# wireless_power_meter.net
KiCad netlist of a schematic drawn in EAGLE
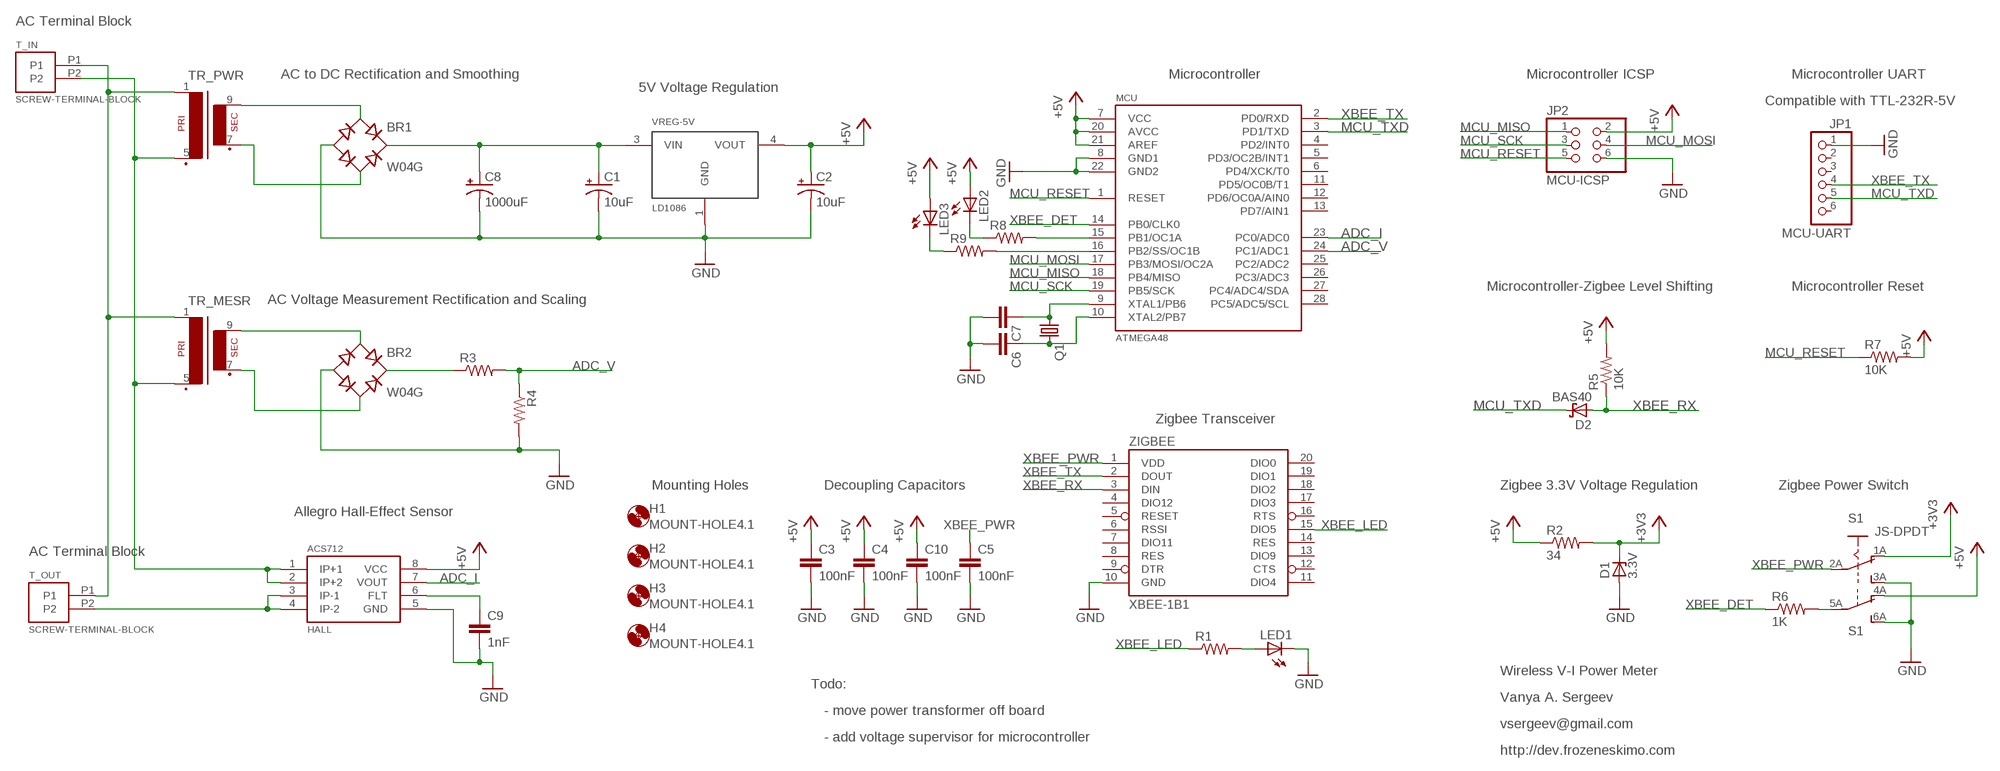
[diagram p0: schematic, sheet 1]

(export (version "E")
  (design (tool "Eeschema 10.0.6"))
  (components
    (comp (ref "BR1")
      (value "W04G")
      (footprint "eagle-import:WOG")
      (libsource (lib "eagle-import") (part "WG04"))
    )
    (comp (ref "BR2")
      (value "W04G")
      (footprint "eagle-import:WOG")
      (libsource (lib "eagle-import") (part "WG04"))
    )
    (comp (ref "C1")
      (value "10uF")
      (footprint "eagle-import:E2,5-5")
      (libsource (lib "eagle-import") (part "CPOL-USE2.5-5"))
    )
    (comp (ref "C2")
      (value "10uF")
      (footprint "eagle-import:E2,5-5")
      (libsource (lib "eagle-import") (part "CPOL-USE2.5-5"))
    )
    (comp (ref "C3")
      (value "100nF")
      (footprint "eagle-import:C0805")
      (libsource (lib "eagle-import") (part "C-EUC0805"))
    )
    (comp (ref "C4")
      (value "100nF")
      (footprint "eagle-import:C0805")
      (libsource (lib "eagle-import") (part "C-EUC0805"))
    )
    (comp (ref "C5")
      (value "100nF")
      (footprint "eagle-import:C0805")
      (libsource (lib "eagle-import") (part "C-EUC0805"))
    )
    (comp (ref "C6")
      (value "C-EUC0805")
      (footprint "eagle-import:C0805")
      (libsource (lib "eagle-import") (part "C-EUC0805"))
    )
    (comp (ref "C7")
      (value "C-EUC0805")
      (footprint "eagle-import:C0805")
      (libsource (lib "eagle-import") (part "C-EUC0805"))
    )
    (comp (ref "C8")
      (value "1000uF")
      (footprint "eagle-import:E5-13")
      (libsource (lib "eagle-import") (part "CPOL-USE5-13"))
    )
    (comp (ref "C9")
      (value "1nF")
      (footprint "eagle-import:C0805")
      (libsource (lib "eagle-import") (part "C-EUC0805"))
    )
    (comp (ref "C10")
      (value "100nF")
      (footprint "eagle-import:C0805")
      (libsource (lib "eagle-import") (part "C-EUC0805"))
    )
    (comp (ref "D1")
      (value "3.3V")
      (footprint "eagle-import:SOT23")
      (libsource (lib "eagle-import") (part "ZENER-DIODESOT23"))
    )
    (comp (ref "D2")
      (value "BAS40")
      (footprint "eagle-import:SOT23")
      (libsource (lib "eagle-import") (part "BAS40"))
    )
    (comp (ref "H1")
      (value "MOUNT-HOLE4.1")
      (footprint "eagle-import:4,1")
      (libsource (lib "eagle-import") (part "MOUNT-HOLE4.1"))
    )
    (comp (ref "H2")
      (value "MOUNT-HOLE4.1")
      (footprint "eagle-import:4,1")
      (libsource (lib "eagle-import") (part "MOUNT-HOLE4.1"))
    )
    (comp (ref "H3")
      (value "MOUNT-HOLE4.1")
      (footprint "eagle-import:4,1")
      (libsource (lib "eagle-import") (part "MOUNT-HOLE4.1"))
    )
    (comp (ref "H4")
      (value "MOUNT-HOLE4.1")
      (footprint "eagle-import:4,1")
      (libsource (lib "eagle-import") (part "MOUNT-HOLE4.1"))
    )
    (comp (ref "HALL")
      (value "ACS712")
      (footprint "eagle-import:SO8")
      (libsource (lib "eagle-import") (part "ACS712"))
    )
    (comp (ref "JP1")
      (value "MCU-UART")
      (footprint "eagle-import:1X06")
      (libsource (lib "eagle-import") (part "PINHD-1X6"))
    )
    (comp (ref "JP2")
      (value "MCU-ICSP")
      (footprint "eagle-import:2X03")
      (libsource (lib "eagle-import") (part "PINHD-2X3"))
    )
    (comp (ref "LED1")
      (value "LEDCHIPLED_0805")
      (footprint "eagle-import:CHIPLED_0805")
      (libsource (lib "eagle-import") (part "LEDCHIPLED_0805"))
    )
    (comp (ref "LED2")
      (value "LEDCHIPLED_0805")
      (footprint "eagle-import:CHIPLED_0805")
      (libsource (lib "eagle-import") (part "LEDCHIPLED_0805"))
    )
    (comp (ref "LED3")
      (value "LEDCHIPLED_0805")
      (footprint "eagle-import:CHIPLED_0805")
      (libsource (lib "eagle-import") (part "LEDCHIPLED_0805"))
    )
    (comp (ref "MCU")
      (value "ATMEGA48")
      (footprint "eagle-import:DIL28-3")
      (libsource (lib "eagle-import") (part "ATMEGA48"))
    )
    (comp (ref "Q1")
      (value "CRYSTALTC26H")
      (footprint "eagle-import:TC26H")
      (libsource (lib "eagle-import") (part "CRYSTALTC26H"))
    )
    (comp (ref "R1")
      (value "R-US_R0805")
      (footprint "eagle-import:R0805")
      (libsource (lib "eagle-import") (part "R-US_R0805"))
    )
    (comp (ref "R2")
      (value "34")
      (footprint "eagle-import:R0805")
      (libsource (lib "eagle-import") (part "R-US_R0805"))
    )
    (comp (ref "R3")
      (value "R-US_R0805")
      (footprint "eagle-import:R0805")
      (libsource (lib "eagle-import") (part "R-US_R0805"))
    )
    (comp (ref "R4")
      (value "R-US_R0805")
      (footprint "eagle-import:R0805")
      (libsource (lib "eagle-import") (part "R-US_R0805"))
    )
    (comp (ref "R5")
      (value "10K")
      (footprint "eagle-import:R0805")
      (libsource (lib "eagle-import") (part "R-US_R0805"))
    )
    (comp (ref "R6")
      (value "1K")
      (footprint "eagle-import:R0805")
      (libsource (lib "eagle-import") (part "R-US_R0805"))
    )
    (comp (ref "R7")
      (value "10K")
      (footprint "eagle-import:R0805")
      (libsource (lib "eagle-import") (part "R-US_R0805"))
    )
    (comp (ref "R8")
      (value "R-US_R0805")
      (footprint "eagle-import:R0805")
      (libsource (lib "eagle-import") (part "R-US_R0805"))
    )
    (comp (ref "R9")
      (value "R-US_R0805")
      (footprint "eagle-import:R0805")
      (libsource (lib "eagle-import") (part "R-US_R0805"))
    )
    (comp (ref "S1")
      (value "JS-DPDT")
      (footprint "eagle-import:JS-MINI-SLIDE")
      (libsource (lib "eagle-import") (part "JS-DPDT"))
    )
    (comp (ref "TR_MESR")
      (value "EI30-1")
      (footprint "eagle-import:EI30-1")
      (libsource (lib "eagle-import") (part "EI30-1"))
    )
    (comp (ref "TR_PWR")
      (value "EI30-1")
      (footprint "eagle-import:EI30-1")
      (libsource (lib "eagle-import") (part "EI30-1"))
    )
    (comp (ref "T_IN")
      (value "SCREW-TERMINAL-BLOCK")
      (footprint "eagle-import:TERMINAL-BLOCK")
      (libsource (lib "eagle-import") (part "SCREW-TERMINAL-BLOCK"))
    )
    (comp (ref "T_OUT")
      (value "SCREW-TERMINAL-BLOCK")
      (footprint "eagle-import:TERMINAL-BLOCK")
      (libsource (lib "eagle-import") (part "SCREW-TERMINAL-BLOCK"))
    )
    (comp (ref "VREG-5V")
      (value "LD1086")
      (footprint "eagle-import:DPACK")
      (libsource (lib "eagle-import") (part "LD1086"))
    )
    (comp (ref "ZIGBEE")
      (value "XBEE-1B1")
      (footprint "eagle-import:XBEE-1")
      (libsource (lib "eagle-import") (part "XBEE-1B1"))
    )
  )
  (nets
    (net (code "1") (name "+3V3") (class "Default")
      (node (ref "D1") (pin "3") (pinfunction "C_3") (pintype "passive"))
      (node (ref "R2") (pin "2") (pinfunction "2_2") (pintype "passive"))
      (node (ref "S1") (pin "1A") (pinfunction "O_1A") (pintype "passive"))
    )
    (net (code "2") (name "+5V") (class "Default")
      (node (ref "C10") (pin "1") (pinfunction "1_1") (pintype "passive"))
      (node (ref "C2") (pin "+") (pinfunction "+_+") (pintype "passive"))
      (node (ref "C3") (pin "1") (pinfunction "1_1") (pintype "passive"))
      (node (ref "C4") (pin "1") (pinfunction "1_1") (pintype "passive"))
      (node (ref "HALL") (pin "8") (pinfunction "VCC_8") (pintype "bidirectional"))
      (node (ref "JP2") (pin "2") (pinfunction "2_2") (pintype "passive"))
      (node (ref "LED2") (pin "A") (pinfunction "A_A") (pintype "passive"))
      (node (ref "LED3") (pin "A") (pinfunction "A_A") (pintype "passive"))
      (node (ref "MCU") (pin "20") (pinfunction "AVCC_20") (pintype "bidirectional"))
      (node (ref "MCU") (pin "21") (pinfunction "AREF_21") (pintype "bidirectional"))
      (node (ref "MCU") (pin "7") (pinfunction "VCC_7") (pintype "bidirectional"))
      (node (ref "R2") (pin "1") (pinfunction "1_1") (pintype "passive"))
      (node (ref "R5") (pin "2") (pinfunction "2_2") (pintype "passive"))
      (node (ref "R7") (pin "2") (pinfunction "2_2") (pintype "passive"))
      (node (ref "S1") (pin "4A") (pinfunction "O_4A") (pintype "passive"))
      (node (ref "VREG-5V") (pin "4") (pinfunction "VOUT_4") (pintype "bidirectional"))
    )
    (net (code "3") (name "/ADC_I") (class "Default")
      (node (ref "HALL") (pin "7") (pinfunction "VOUT_7") (pintype "bidirectional"))
      (node (ref "MCU") (pin "23") (pinfunction "PC0/ADC0_23") (pintype "bidirectional"))
    )
    (net (code "4") (name "/ADC_V") (class "Default")
      (node (ref "MCU") (pin "24") (pinfunction "PC1/ADC1_24") (pintype "bidirectional"))
      (node (ref "R3") (pin "2") (pinfunction "2_2") (pintype "passive"))
      (node (ref "R4") (pin "1") (pinfunction "1_1") (pintype "passive"))
    )
    (net (code "5") (name "/MCU_MISO") (class "Default")
      (node (ref "JP2") (pin "1") (pinfunction "1_1") (pintype "passive"))
      (node (ref "MCU") (pin "18") (pinfunction "PB4/MISO_18") (pintype "bidirectional"))
    )
    (net (code "6") (name "/MCU_MOSI") (class "Default")
      (node (ref "JP2") (pin "4") (pinfunction "4_4") (pintype "passive"))
      (node (ref "MCU") (pin "17") (pinfunction "PB3/MOSI/OC2A_17") (pintype "bidirectional"))
    )
    (net (code "7") (name "/MCU_RESET") (class "Default")
      (node (ref "JP2") (pin "5") (pinfunction "5_5") (pintype "passive"))
      (node (ref "MCU") (pin "1") (pinfunction "RESET_1") (pintype "bidirectional"))
      (node (ref "R7") (pin "1") (pinfunction "1_1") (pintype "passive"))
    )
    (net (code "8") (name "/MCU_SCK") (class "Default")
      (node (ref "JP2") (pin "3") (pinfunction "3_3") (pintype "passive"))
      (node (ref "MCU") (pin "19") (pinfunction "PB5/SCK_19") (pintype "bidirectional"))
    )
    (net (code "9") (name "/MCU_TXD") (class "Default")
      (node (ref "D2") (pin "3") (pinfunction "C_3") (pintype "passive"))
      (node (ref "JP1") (pin "5") (pinfunction "5_5") (pintype "passive"))
      (node (ref "MCU") (pin "3") (pinfunction "PD1/TXD_3") (pintype "bidirectional"))
    )
    (net (code "10") (name "/XBEE_DET") (class "Default")
      (node (ref "MCU") (pin "14") (pinfunction "PB0/CLK0_14") (pintype "bidirectional"))
      (node (ref "R6") (pin "1") (pinfunction "1_1") (pintype "passive"))
    )
    (net (code "11") (name "/XBEE_LED") (class "Default")
      (node (ref "R1") (pin "1") (pinfunction "1_1") (pintype "passive"))
      (node (ref "ZIGBEE") (pin "15") (pinfunction "DIO5_15") (pintype "bidirectional"))
    )
    (net (code "12") (name "/XBEE_PWR") (class "Default")
      (node (ref "C5") (pin "1") (pinfunction "1_1") (pintype "passive"))
      (node (ref "S1") (pin "2A") (pinfunction "P_2A") (pintype "passive"))
      (node (ref "ZIGBEE") (pin "1") (pinfunction "VDD_1") (pintype "power_in"))
    )
    (net (code "13") (name "/XBEE_RX") (class "Default")
      (node (ref "D2") (pin "1") (pinfunction "A_1") (pintype "passive"))
      (node (ref "R5") (pin "1") (pinfunction "1_1") (pintype "passive"))
      (node (ref "ZIGBEE") (pin "3") (pinfunction "DIN_3") (pintype "input"))
    )
    (net (code "14") (name "/XBEE_TX") (class "Default")
      (node (ref "JP1") (pin "4") (pinfunction "4_4") (pintype "passive"))
      (node (ref "MCU") (pin "2") (pinfunction "PD0/RXD_2") (pintype "bidirectional"))
      (node (ref "ZIGBEE") (pin "2") (pinfunction "DOUT_2") (pintype "output"))
    )
    (net (code "15") (name "GND") (class "Default")
      (node (ref "BR1") (pin "-") (pinfunction "-_-") (pintype "passive"))
      (node (ref "BR2") (pin "-") (pinfunction "-_-") (pintype "passive"))
      (node (ref "C1") (pin "-") (pinfunction "-_-") (pintype "passive"))
      (node (ref "C10") (pin "2") (pinfunction "2_2") (pintype "passive"))
      (node (ref "C2") (pin "-") (pinfunction "-_-") (pintype "passive"))
      (node (ref "C3") (pin "2") (pinfunction "2_2") (pintype "passive"))
      (node (ref "C4") (pin "2") (pinfunction "2_2") (pintype "passive"))
      (node (ref "C5") (pin "2") (pinfunction "2_2") (pintype "passive"))
      (node (ref "C6") (pin "2") (pinfunction "2_2") (pintype "passive"))
      (node (ref "C7") (pin "2") (pinfunction "2_2") (pintype "passive"))
      (node (ref "C8") (pin "-") (pinfunction "-_-") (pintype "passive"))
      (node (ref "C9") (pin "2") (pinfunction "2_2") (pintype "passive"))
      (node (ref "D1") (pin "1") (pinfunction "A_1") (pintype "passive"))
      (node (ref "HALL") (pin "5") (pinfunction "GND_5") (pintype "bidirectional"))
      (node (ref "JP1") (pin "1") (pinfunction "1_1") (pintype "passive"))
      (node (ref "JP2") (pin "6") (pinfunction "6_6") (pintype "passive"))
      (node (ref "LED1") (pin "C") (pinfunction "C_C") (pintype "passive"))
      (node (ref "MCU") (pin "22") (pinfunction "GND2_22") (pintype "bidirectional"))
      (node (ref "MCU") (pin "8") (pinfunction "GND1_8") (pintype "bidirectional"))
      (node (ref "R4") (pin "2") (pinfunction "2_2") (pintype "passive"))
      (node (ref "S1") (pin "3A") (pinfunction "S_3A") (pintype "passive"))
      (node (ref "S1") (pin "6A") (pinfunction "S_6A") (pintype "passive"))
      (node (ref "VREG-5V") (pin "1") (pinfunction "GND_1") (pintype "bidirectional"))
      (node (ref "ZIGBEE") (pin "10") (pinfunction "GND_10") (pintype "power_in"))
    )
    (net (code "16") (name "Net-(BR2-Pad+)") (class "Default")
      (node (ref "BR2") (pin "+") (pinfunction "+_+") (pintype "passive"))
      (node (ref "R3") (pin "1") (pinfunction "1_1") (pintype "passive"))
    )
    (net (code "17") (name "Net-(HALL-FLT)") (class "Default")
      (node (ref "C9") (pin "1") (pinfunction "1_1") (pintype "passive"))
      (node (ref "HALL") (pin "6") (pinfunction "FLT_6") (pintype "bidirectional"))
    )
    (net (code "18") (name "Net-(HALL-IP+1)") (class "Default")
      (node (ref "HALL") (pin "1") (pinfunction "IP+1_1") (pintype "bidirectional"))
      (node (ref "HALL") (pin "2") (pinfunction "IP+2_2") (pintype "bidirectional"))
      (node (ref "TR_MESR") (pin "5") (pinfunction "P2_5") (pintype "passive"))
      (node (ref "TR_PWR") (pin "5") (pinfunction "P2_5") (pintype "passive"))
      (node (ref "T_IN") (pin "P2") (pinfunction "P2_P2") (pintype "bidirectional"))
    )
    (net (code "19") (name "Net-(HALL-IP-1)") (class "Default")
      (node (ref "HALL") (pin "3") (pinfunction "IP-1_3") (pintype "bidirectional"))
      (node (ref "HALL") (pin "4") (pinfunction "IP-2_4") (pintype "bidirectional"))
      (node (ref "T_OUT") (pin "P2") (pinfunction "P2_P2") (pintype "bidirectional"))
    )
    (net (code "20") (name "Net-(LED1-PadA)") (class "Default")
      (node (ref "LED1") (pin "A") (pinfunction "A_A") (pintype "passive"))
      (node (ref "R1") (pin "2") (pinfunction "2_2") (pintype "passive"))
    )
    (net (code "21") (name "Net-(LED2-PadC)") (class "Default")
      (node (ref "LED2") (pin "C") (pinfunction "C_C") (pintype "passive"))
      (node (ref "R8") (pin "1") (pinfunction "1_1") (pintype "passive"))
    )
    (net (code "22") (name "Net-(LED3-PadC)") (class "Default")
      (node (ref "LED3") (pin "C") (pinfunction "C_C") (pintype "passive"))
      (node (ref "R9") (pin "1") (pinfunction "1_1") (pintype "passive"))
    )
    (net (code "23") (name "Net-(MCU-PB1{slash}OC1A)") (class "Default")
      (node (ref "MCU") (pin "15") (pinfunction "PB1/OC1A_15") (pintype "bidirectional"))
      (node (ref "R8") (pin "2") (pinfunction "2_2") (pintype "passive"))
    )
    (net (code "24") (name "Net-(MCU-PB2{slash}SS{slash}OC1B)") (class "Default")
      (node (ref "MCU") (pin "16") (pinfunction "PB2/SS/OC1B_16") (pintype "bidirectional"))
      (node (ref "R9") (pin "2") (pinfunction "2_2") (pintype "passive"))
    )
    (net (code "25") (name "Net-(MCU-XTAL1{slash}PB6)") (class "Default")
      (node (ref "C7") (pin "1") (pinfunction "1_1") (pintype "passive"))
      (node (ref "MCU") (pin "9") (pinfunction "XTAL1/PB6_9") (pintype "bidirectional"))
      (node (ref "Q1") (pin "1") (pinfunction "1_1") (pintype "passive"))
    )
    (net (code "26") (name "Net-(MCU-XTAL2{slash}PB7)") (class "Default")
      (node (ref "C6") (pin "1") (pinfunction "1_1") (pintype "passive"))
      (node (ref "MCU") (pin "10") (pinfunction "XTAL2/PB7_10") (pintype "bidirectional"))
      (node (ref "Q1") (pin "2") (pinfunction "2_2") (pintype "passive"))
    )
    (net (code "27") (name "Net-(S1A-P)") (class "Default")
      (node (ref "R6") (pin "2") (pinfunction "2_2") (pintype "passive"))
      (node (ref "S1") (pin "5A") (pinfunction "P_5A") (pintype "passive"))
    )
    (net (code "28") (name "Net-(TR_MESR-P1)") (class "Default")
      (node (ref "TR_MESR") (pin "1") (pinfunction "P1_1") (pintype "passive"))
      (node (ref "TR_PWR") (pin "1") (pinfunction "P1_1") (pintype "passive"))
      (node (ref "T_IN") (pin "P1") (pinfunction "P1_P1") (pintype "bidirectional"))
      (node (ref "T_OUT") (pin "P1") (pinfunction "P1_P1") (pintype "bidirectional"))
    )
    (net (code "29") (name "Net-(TR_MESR-S3)") (class "Default")
      (node (ref "BR2") (pin "AC2") (pinfunction "AC2_AC2") (pintype "passive"))
      (node (ref "TR_MESR") (pin "7") (pinfunction "S3_7") (pintype "passive"))
    )
    (net (code "30") (name "Net-(TR_MESR-S4)") (class "Default")
      (node (ref "BR2") (pin "AC1") (pinfunction "AC1_AC1") (pintype "passive"))
      (node (ref "TR_MESR") (pin "9") (pinfunction "S4_9") (pintype "passive"))
    )
    (net (code "31") (name "Net-(TR_PWR-S3)") (class "Default")
      (node (ref "BR1") (pin "AC2") (pinfunction "AC2_AC2") (pintype "passive"))
      (node (ref "TR_PWR") (pin "7") (pinfunction "S3_7") (pintype "passive"))
    )
    (net (code "32") (name "Net-(TR_PWR-S4)") (class "Default")
      (node (ref "BR1") (pin "AC1") (pinfunction "AC1_AC1") (pintype "passive"))
      (node (ref "TR_PWR") (pin "9") (pinfunction "S4_9") (pintype "passive"))
    )
    (net (code "33") (name "Net-(VREG-5V-VIN)") (class "Default")
      (node (ref "BR1") (pin "+") (pinfunction "+_+") (pintype "passive"))
      (node (ref "C1") (pin "+") (pinfunction "+_+") (pintype "passive"))
      (node (ref "C8") (pin "+") (pinfunction "+_+") (pintype "passive"))
      (node (ref "VREG-5V") (pin "3") (pinfunction "VIN_3") (pintype "bidirectional"))
    )
    (net (code "34") (name "unconnected-(JP1-Pad2)") (class "Default")
      (node (ref "JP1") (pin "2") (pinfunction "2_2") (pintype "passive"))
    )
    (net (code "35") (name "unconnected-(JP1-Pad3)") (class "Default")
      (node (ref "JP1") (pin "3") (pinfunction "3_3") (pintype "passive"))
    )
    (net (code "36") (name "unconnected-(JP1-Pad6)") (class "Default")
      (node (ref "JP1") (pin "6") (pinfunction "6_6") (pintype "passive"))
    )
    (net (code "37") (name "unconnected-(MCU-PC2{slash}ADC2-Pad25)") (class "Default")
      (node (ref "MCU") (pin "25") (pinfunction "PC2/ADC2_25") (pintype "bidirectional"))
    )
    (net (code "38") (name "unconnected-(MCU-PC3{slash}ADC3-Pad26)") (class "Default")
      (node (ref "MCU") (pin "26") (pinfunction "PC3/ADC3_26") (pintype "bidirectional"))
    )
    (net (code "39") (name "unconnected-(MCU-PC4{slash}ADC4{slash}SDA-Pad27)") (class "Default")
      (node (ref "MCU") (pin "27") (pinfunction "PC4/ADC4/SDA_27") (pintype "bidirectional"))
    )
    (net (code "40") (name "unconnected-(MCU-PC5{slash}ADC5{slash}SCL-Pad28)") (class "Default")
      (node (ref "MCU") (pin "28") (pinfunction "PC5/ADC5/SCL_28") (pintype "bidirectional"))
    )
    (net (code "41") (name "unconnected-(MCU-PD2{slash}INT0-Pad4)") (class "Default")
      (node (ref "MCU") (pin "4") (pinfunction "PD2/INT0_4") (pintype "bidirectional"))
    )
    (net (code "42") (name "unconnected-(MCU-PD3{slash}OC2B{slash}INT1-Pad5)") (class "Default")
      (node (ref "MCU") (pin "5") (pinfunction "PD3/OC2B/INT1_5") (pintype "bidirectional"))
    )
    (net (code "43") (name "unconnected-(MCU-PD4{slash}XCK{slash}T0-Pad6)") (class "Default")
      (node (ref "MCU") (pin "6") (pinfunction "PD4/XCK/T0_6") (pintype "bidirectional"))
    )
    (net (code "44") (name "unconnected-(MCU-PD5{slash}OC0B{slash}T1-Pad11)") (class "Default")
      (node (ref "MCU") (pin "11") (pinfunction "PD5/OC0B/T1_11") (pintype "bidirectional"))
    )
    (net (code "45") (name "unconnected-(MCU-PD6{slash}OC0A{slash}AIN0-Pad12)") (class "Default")
      (node (ref "MCU") (pin "12") (pinfunction "PD6/OC0A/AIN0_12") (pintype "bidirectional"))
    )
    (net (code "46") (name "unconnected-(MCU-PD7{slash}AIN1-Pad13)") (class "Default")
      (node (ref "MCU") (pin "13") (pinfunction "PD7/AIN1_13") (pintype "bidirectional"))
    )
    (net (code "47") (name "unconnected-(ZIGBEE-CTS-Pad12)") (class "Default")
      (node (ref "ZIGBEE") (pin "12") (pinfunction "CTS_12") (pintype "output"))
    )
    (net (code "48") (name "unconnected-(ZIGBEE-DIO0-Pad20)") (class "Default")
      (node (ref "ZIGBEE") (pin "20") (pinfunction "DIO0_20") (pintype "bidirectional"))
    )
    (net (code "49") (name "unconnected-(ZIGBEE-DIO1-Pad19)") (class "Default")
      (node (ref "ZIGBEE") (pin "19") (pinfunction "DIO1_19") (pintype "bidirectional"))
    )
    (net (code "50") (name "unconnected-(ZIGBEE-DIO2-Pad18)") (class "Default")
      (node (ref "ZIGBEE") (pin "18") (pinfunction "DIO2_18") (pintype "bidirectional"))
    )
    (net (code "51") (name "unconnected-(ZIGBEE-DIO3-Pad17)") (class "Default")
      (node (ref "ZIGBEE") (pin "17") (pinfunction "DIO3_17") (pintype "bidirectional"))
    )
    (net (code "52") (name "unconnected-(ZIGBEE-DIO4-Pad11)") (class "Default")
      (node (ref "ZIGBEE") (pin "11") (pinfunction "DIO4_11") (pintype "bidirectional"))
    )
    (net (code "53") (name "unconnected-(ZIGBEE-DIO9-Pad13)") (class "Default")
      (node (ref "ZIGBEE") (pin "13") (pinfunction "DIO9_13") (pintype "bidirectional"))
    )
    (net (code "54") (name "unconnected-(ZIGBEE-DIO11-Pad7)") (class "Default")
      (node (ref "ZIGBEE") (pin "7") (pinfunction "DIO11_7") (pintype "bidirectional"))
    )
    (net (code "55") (name "unconnected-(ZIGBEE-DIO12-Pad4)") (class "Default")
      (node (ref "ZIGBEE") (pin "4") (pinfunction "DIO12_4") (pintype "bidirectional"))
    )
    (net (code "56") (name "unconnected-(ZIGBEE-DTR-Pad9)") (class "Default")
      (node (ref "ZIGBEE") (pin "9") (pinfunction "DTR_9") (pintype "bidirectional"))
    )
    (net (code "57") (name "unconnected-(ZIGBEE-RES-Pad8)") (class "Default")
      (node (ref "ZIGBEE") (pin "8") (pinfunction "RES_8") (pintype "bidirectional"))
    )
    (net (code "58") (name "unconnected-(ZIGBEE-RES-Pad14)") (class "Default")
      (node (ref "ZIGBEE") (pin "14") (pinfunction "RES_14") (pintype "bidirectional"))
    )
    (net (code "59") (name "unconnected-(ZIGBEE-RESET-Pad5)") (class "Default")
      (node (ref "ZIGBEE") (pin "5") (pinfunction "RESET_5") (pintype "input"))
    )
    (net (code "60") (name "unconnected-(ZIGBEE-RSSI-Pad6)") (class "Default")
      (node (ref "ZIGBEE") (pin "6") (pinfunction "RSSI_6") (pintype "bidirectional"))
    )
    (net (code "61") (name "unconnected-(ZIGBEE-RTS-Pad16)") (class "Default")
      (node (ref "ZIGBEE") (pin "16") (pinfunction "RTS_16") (pintype "input"))
    )
  )
)
